# SCH_Power_board_2023-06-05.net
KiCad netlist of a schematic drawn in EasyEDA
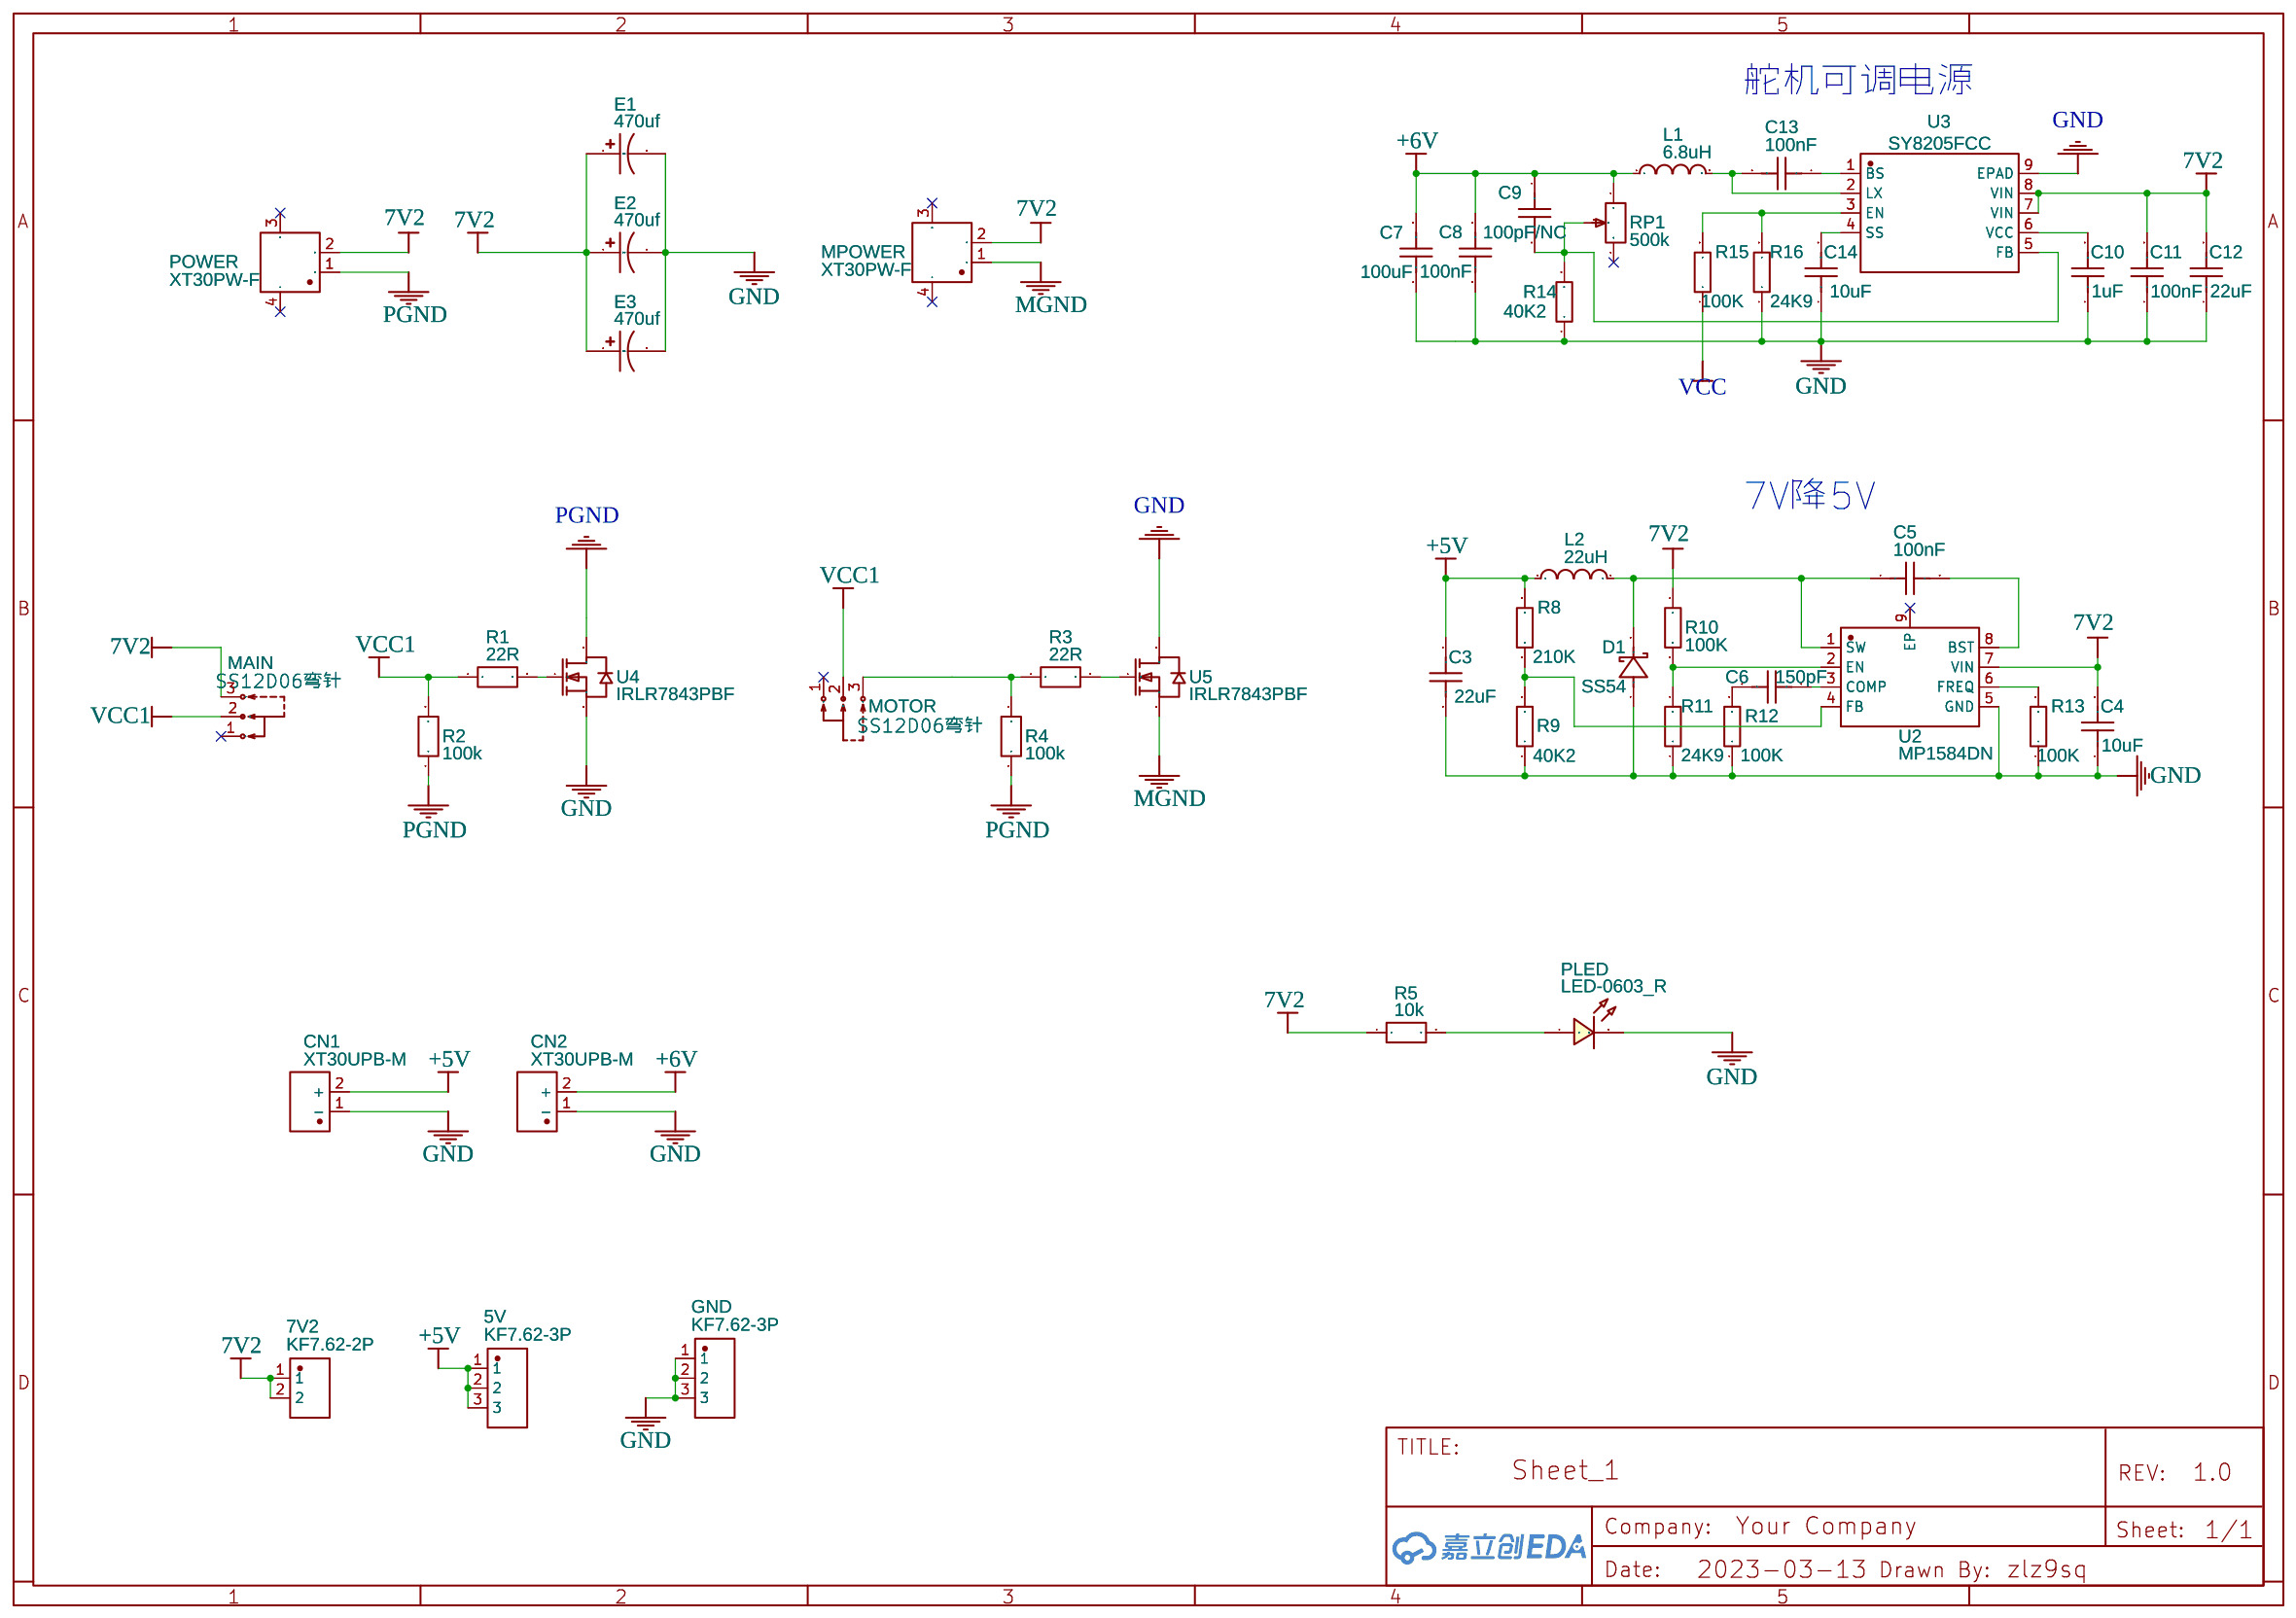
[diagram p0: schematic sheet]

(export (version "E")
  (design (tool "Eeschema 10.0.6"))
  (components
    (comp (ref "5V")
      (value "KF7.62-3P")
      (fields (field (name "BOM_Supplier Part") "C707825"))
      (libsource (lib "") (part "KF7.62-3P"))
    )
    (comp (ref "7V2")
      (value "KF7.62-2P")
      (fields (field (name "BOM_Supplier Part") "C707824"))
      (libsource (lib "") (part "KF7.62-2P"))
    )
    (comp (ref "C3") (value "22uF") (libsource (lib "") (part "C_0603_US_1")))
    (comp (ref "C4") (value "10uF") (libsource (lib "") (part "C_0603_US")))
    (comp (ref "C5") (value "100nF") (libsource (lib "") (part "C_0603_US_3")))
    (comp (ref "C6") (value "150pF") (libsource (lib "") (part "C_0603_US_2")))
    (comp (ref "C7")
      (value "100uF")
      (fields
        (field (name "BOM_Manufacturer Part") "C1210X7R475K630NT")
        (field (name "BOM_Supplier Part") "C2911397")
      )
      (libsource (lib "") (part "C1210X7R475K630NT"))
    )
    (comp (ref "C8") (value "100nF") (libsource (lib "") (part "C_0603_US_1")))
    (comp (ref "C9") (value "100pF/NC") (libsource (lib "") (part "C_0603_US_1")))
    (comp (ref "C10") (value "1uF") (libsource (lib "") (part "C_0603_US")))
    (comp (ref "C11") (value "100nF") (libsource (lib "") (part "C_0603_US")))
    (comp (ref "C12") (value "22uF") (libsource (lib "") (part "C_0603_US")))
    (comp (ref "C13") (value "100nF") (libsource (lib "") (part "C_0603_US_2")))
    (comp (ref "C14") (value "10uF") (libsource (lib "") (part "C_0603_US")))
    (comp (ref "CN1")
      (value "XT30UPB-M")
      (fields (field (name "BOM_Supplier Part") "C428721"))
      (libsource (lib "") (part "XT30UPB-M"))
    )
    (comp (ref "CN2")
      (value "XT30UPB-M")
      (fields (field (name "BOM_Supplier Part") "C428721"))
      (libsource (lib "") (part "XT30UPB-M"))
    )
    (comp (ref "D1")
      (value "SS54")
      (fields (field (name "BOM_Manufacturer Part") "SS54G") (field (name "BOM_Supplier Part") "C719150"))
      (libsource (lib "") (part "SS54G"))
    )
    (comp (ref "E1") (value "470uf") (libsource (lib "") (part "CE_TH_D5.0×F2.0_US")))
    (comp (ref "E2") (value "470uf") (libsource (lib "") (part "CE_TH_D5.0×F2.0_US")))
    (comp (ref "E3") (value "470uf") (libsource (lib "") (part "CE_TH_D5.0×F2.0_US")))
    (comp (ref "GND")
      (value "KF7.62-3P")
      (fields (field (name "BOM_Supplier Part") "C707825"))
      (libsource (lib "") (part "KF7.62-3P_1"))
    )
    (comp (ref "L1")
      (value "6.8uH")
      (fields
        (field (name "BOM_Manufacturer Part") "FXL0630-8R2-M")
        (field (name "BOM_Supplier Part") "C167222")
      )
      (libsource (lib "") (part "FXL0630-8R2-M"))
    )
    (comp (ref "L2")
      (value "22uH")
      (fields
        (field (name "BOM_Manufacturer Part") "FXL0630-8R2-M")
        (field (name "BOM_Supplier Part") "C167222")
      )
      (libsource (lib "") (part "FXL0630-8R2-M"))
    )
    (comp (ref "MAIN")
      (value "SS12D06弯针")
      (fields (field (name "BOM_Supplier Part") "C9900027365"))
      (libsource (lib "") (part "SS12D06弯针"))
    )
    (comp (ref "MOTOR")
      (value "SS12D06弯针")
      (fields (field (name "BOM_Supplier Part") "C9900027365"))
      (libsource (lib "") (part "SS12D06弯针_1"))
    )
    (comp (ref "MPOWER")
      (value "XT30PW-F")
      (fields (field (name "BOM_Supplier Part") "C2913282"))
      (libsource (lib "") (part "XT30PW-F_1"))
    )
    (comp (ref "PLED")
      (value "LED-0603_R")
      (fields
        (field (name "BOM_Manufacturer Part") "19-217/R6C-AL1M2VY/3T")
        (field (name "BOM_Supplier Part") "C72044")
      )
      (libsource (lib "") (part "LED-0603_R"))
    )
    (comp (ref "POWER")
      (value "XT30PW-F")
      (fields (field (name "BOM_Supplier Part") "C2913282"))
      (libsource (lib "") (part "XT30PW-F"))
    )
    (comp (ref "R1") (value "22R") (libsource (lib "") (part "R_0603_EU")))
    (comp (ref "R2") (value "100k") (libsource (lib "") (part "R_0603_EU_1")))
    (comp (ref "R3") (value "22R") (libsource (lib "") (part "R_0603_EU")))
    (comp (ref "R4") (value "100k") (libsource (lib "") (part "R_0603_EU_1")))
    (comp (ref "R5") (value "10k") (libsource (lib "") (part "R_0603_EU")))
    (comp (ref "R8")
      (value "210K")
      (fields
        (field (name "BOM_Manufacturer Part") "QR0603B47KP05")
        (field (name "BOM_Supplier Part") "C176123")
      )
      (libsource (lib "") (part "QR0603B47KP05"))
    )
    (comp (ref "R9")
      (value "40K2")
      (fields
        (field (name "BOM_Manufacturer Part") "QR0603B47KP05")
        (field (name "BOM_Supplier Part") "C176123")
      )
      (libsource (lib "") (part "QR0603B47KP05"))
    )
    (comp (ref "R10")
      (value "100K")
      (fields
        (field (name "BOM_Manufacturer Part") "QR0603B47KP05")
        (field (name "BOM_Supplier Part") "C176123")
      )
      (libsource (lib "") (part "QR0603B47KP05_1"))
    )
    (comp (ref "R11")
      (value "24K9")
      (fields
        (field (name "BOM_Manufacturer Part") "QR0603B47KP05")
        (field (name "BOM_Supplier Part") "C176123")
      )
      (libsource (lib "") (part "QR0603B47KP05"))
    )
    (comp (ref "R12")
      (value "100K")
      (fields
        (field (name "BOM_Manufacturer Part") "QR0603B47KP05")
        (field (name "BOM_Supplier Part") "C176123")
      )
      (libsource (lib "") (part "QR0603B47KP05"))
    )
    (comp (ref "R13")
      (value "100K")
      (fields
        (field (name "BOM_Manufacturer Part") "QR0603B47KP05")
        (field (name "BOM_Supplier Part") "C176123")
      )
      (libsource (lib "") (part "QR0603B47KP05"))
    )
    (comp (ref "R14")
      (value "40K2")
      (fields
        (field (name "BOM_Manufacturer Part") "QR0603B47KP05")
        (field (name "BOM_Supplier Part") "C176123")
      )
      (libsource (lib "") (part "QR0603B47KP05"))
    )
    (comp (ref "R15")
      (value "100K")
      (fields
        (field (name "BOM_Manufacturer Part") "QR0603B47KP05")
        (field (name "BOM_Supplier Part") "C176123")
      )
      (libsource (lib "") (part "QR0603B47KP05"))
    )
    (comp (ref "R16")
      (value "24K9")
      (fields
        (field (name "BOM_Manufacturer Part") "QR0603B47KP05")
        (field (name "BOM_Supplier Part") "C176123")
      )
      (libsource (lib "") (part "QR0603B47KP05"))
    )
    (comp (ref "RP1")
      (value "500k")
      (fields
        (field (name "BOM_Manufacturer Part") "多圈电位器3296W顶调20K")
        (field (name "BOM_Supplier Part") "C9900006166")
      )
      (libsource (lib "") (part "多圈电位器3296W顶调20K"))
    )
    (comp (ref "U2")
      (value "MP1584DN")
      (fields (field (name "BOM_Supplier Part") "C9900012540"))
      (libsource (lib "") (part "MP1584DN"))
    )
    (comp (ref "U3")
      (value "SY8205FCC")
      (fields (field (name "BOM_Supplier Part") "C111875"))
      (libsource (lib "") (part "SY8205FCC"))
    )
    (comp (ref "U4")
      (value "IRLR7843PBF")
      (fields (field (name "BOM_Supplier Part") "C3294487"))
      (libsource (lib "") (part "IRLR7843PBF"))
    )
    (comp (ref "U5")
      (value "IRLR7843PBF")
      (fields (field (name "BOM_Supplier Part") "C3294487"))
      (libsource (lib "") (part "IRLR7843PBF"))
    )
  )
  (nets
    (net (code "1") (name "+5V") (class "Default")
      (node (ref "5V") (pin "1") (pinfunction "1_1") (pintype "unspecified"))
      (node (ref "5V") (pin "2") (pinfunction "2_2") (pintype "unspecified"))
      (node (ref "5V") (pin "3") (pinfunction "3_3") (pintype "unspecified"))
      (node (ref "C3") (pin "1") (pinfunction "1_1") (pintype "unspecified"))
      (node (ref "CN1") (pin "2") (pinfunction "+_2") (pintype "unspecified"))
      (node (ref "L2") (pin "1") (pinfunction "1_1") (pintype "unspecified"))
      (node (ref "R8") (pin "2") (pinfunction "2_2") (pintype "unspecified"))
    )
    (net (code "2") (name "+6V") (class "Default")
      (node (ref "C7") (pin "2") (pinfunction "2_2") (pintype "unspecified"))
      (node (ref "C8") (pin "1") (pinfunction "1_1") (pintype "unspecified"))
      (node (ref "C9") (pin "1") (pinfunction "1_1") (pintype "unspecified"))
      (node (ref "CN2") (pin "2") (pinfunction "+_2") (pintype "unspecified"))
      (node (ref "L1") (pin "1") (pinfunction "1_1") (pintype "unspecified"))
      (node (ref "RP1") (pin "1") (pinfunction "1_1") (pintype "input"))
    )
    (net (code "3") (name "7V2") (class "Default")
      (node (ref "7V2") (pin "1") (pinfunction "1_1") (pintype "unspecified"))
      (node (ref "7V2") (pin "2") (pinfunction "2_2") (pintype "unspecified"))
      (node (ref "C11") (pin "2") (pinfunction "2_2") (pintype "unspecified"))
      (node (ref "C12") (pin "2") (pinfunction "2_2") (pintype "unspecified"))
      (node (ref "C4") (pin "2") (pinfunction "2_2") (pintype "unspecified"))
      (node (ref "E1") (pin "1") (pinfunction "1_1") (pintype "unspecified"))
      (node (ref "E2") (pin "1") (pinfunction "1_1") (pintype "unspecified"))
      (node (ref "E3") (pin "1") (pinfunction "1_1") (pintype "unspecified"))
      (node (ref "MAIN") (pin "3") (pinfunction "3_3") (pintype "unspecified"))
      (node (ref "MPOWER") (pin "2") (pinfunction "2_2") (pintype "unspecified"))
      (node (ref "POWER") (pin "2") (pinfunction "2_2") (pintype "unspecified"))
      (node (ref "R10") (pin "1") (pinfunction "1_1") (pintype "unspecified"))
      (node (ref "R5") (pin "1") (pinfunction "1_1") (pintype "unspecified"))
      (node (ref "U2") (pin "7") (pinfunction "VIN_7") (pintype "unspecified"))
      (node (ref "U3") (pin "7") (pinfunction "VIN_7") (pintype "unspecified"))
      (node (ref "U3") (pin "8") (pinfunction "VIN_8") (pintype "unspecified"))
    )
    (net (code "4") (name "GND") (class "Default")
      (node (ref "C10") (pin "1") (pinfunction "1_1") (pintype "unspecified"))
      (node (ref "C11") (pin "1") (pinfunction "1_1") (pintype "unspecified"))
      (node (ref "C12") (pin "1") (pinfunction "1_1") (pintype "unspecified"))
      (node (ref "C14") (pin "1") (pinfunction "1_1") (pintype "unspecified"))
      (node (ref "C3") (pin "2") (pinfunction "2_2") (pintype "unspecified"))
      (node (ref "C4") (pin "1") (pinfunction "1_1") (pintype "unspecified"))
      (node (ref "C7") (pin "1") (pinfunction "1_1") (pintype "unspecified"))
      (node (ref "C8") (pin "2") (pinfunction "2_2") (pintype "unspecified"))
      (node (ref "CN1") (pin "1") (pinfunction "-_1") (pintype "unspecified"))
      (node (ref "CN2") (pin "1") (pinfunction "-_1") (pintype "unspecified"))
      (node (ref "D1") (pin "1") (pinfunction "A_1") (pintype "unspecified"))
      (node (ref "E1") (pin "2") (pinfunction "2_2") (pintype "unspecified"))
      (node (ref "E2") (pin "2") (pinfunction "2_2") (pintype "unspecified"))
      (node (ref "E3") (pin "2") (pinfunction "2_2") (pintype "unspecified"))
      (node (ref "GND") (pin "1") (pinfunction "1_1") (pintype "unspecified"))
      (node (ref "GND") (pin "2") (pinfunction "2_2") (pintype "unspecified"))
      (node (ref "GND") (pin "3") (pinfunction "3_3") (pintype "unspecified"))
      (node (ref "PLED") (pin "2") (pinfunction "2_2") (pintype "unspecified"))
      (node (ref "R11") (pin "1") (pinfunction "1_1") (pintype "unspecified"))
      (node (ref "R12") (pin "1") (pinfunction "1_1") (pintype "unspecified"))
      (node (ref "R13") (pin "1") (pinfunction "1_1") (pintype "unspecified"))
      (node (ref "R14") (pin "1") (pinfunction "1_1") (pintype "unspecified"))
      (node (ref "R16") (pin "1") (pinfunction "1_1") (pintype "unspecified"))
      (node (ref "R9") (pin "1") (pinfunction "1_1") (pintype "unspecified"))
      (node (ref "U2") (pin "5") (pinfunction "GND_5") (pintype "unspecified"))
      (node (ref "U3") (pin "9") (pinfunction "EPAD_9") (pintype "unspecified"))
      (node (ref "U4") (pin "3") (pinfunction "S_3") (pintype "unspecified"))
      (node (ref "U5") (pin "2") (pinfunction "D_2") (pintype "unspecified"))
    )
    (net (code "5") (name "MGND") (class "Default")
      (node (ref "MPOWER") (pin "1") (pinfunction "1_1") (pintype "unspecified"))
      (node (ref "U5") (pin "3") (pinfunction "S_3") (pintype "unspecified"))
    )
    (net (code "6") (name "Net-(C6-Pad2)") (class "Default")
      (node (ref "C6") (pin "2") (pinfunction "2_2") (pintype "unspecified"))
      (node (ref "R12") (pin "2") (pinfunction "2_2") (pintype "unspecified"))
    )
    (net (code "7") (name "Net-(D1-K)") (class "Default")
      (node (ref "C5") (pin "1") (pinfunction "1_1") (pintype "unspecified"))
      (node (ref "D1") (pin "2") (pinfunction "K_2") (pintype "unspecified"))
      (node (ref "L2") (pin "2") (pinfunction "2_2") (pintype "unspecified"))
      (node (ref "U2") (pin "1") (pinfunction "SW_1") (pintype "unspecified"))
    )
    (net (code "8") (name "Net-(MOTOR-Pad3)") (class "Default")
      (node (ref "MOTOR") (pin "3") (pinfunction "3_3") (pintype "unspecified"))
      (node (ref "R3") (pin "1") (pinfunction "1_1") (pintype "unspecified"))
      (node (ref "R4") (pin "2") (pinfunction "2_2") (pintype "unspecified"))
    )
    (net (code "9") (name "Net-(PLED-Pad1)") (class "Default")
      (node (ref "PLED") (pin "1") (pinfunction "1_1") (pintype "unspecified"))
      (node (ref "R5") (pin "2") (pinfunction "2_2") (pintype "unspecified"))
    )
    (net (code "10") (name "Net-(U2-BST)") (class "Default")
      (node (ref "C5") (pin "2") (pinfunction "2_2") (pintype "unspecified"))
      (node (ref "U2") (pin "8") (pinfunction "BST_8") (pintype "unspecified"))
    )
    (net (code "11") (name "Net-(U2-COMP)") (class "Default")
      (node (ref "C6") (pin "1") (pinfunction "1_1") (pintype "unspecified"))
      (node (ref "U2") (pin "3") (pinfunction "COMP_3") (pintype "unspecified"))
    )
    (net (code "12") (name "Net-(U2-EN)") (class "Default")
      (node (ref "R10") (pin "2") (pinfunction "2_2") (pintype "unspecified"))
      (node (ref "R11") (pin "2") (pinfunction "2_2") (pintype "unspecified"))
      (node (ref "U2") (pin "2") (pinfunction "EN_2") (pintype "unspecified"))
    )
    (net (code "13") (name "Net-(U2-FB)") (class "Default")
      (node (ref "R8") (pin "1") (pinfunction "1_1") (pintype "unspecified"))
      (node (ref "R9") (pin "2") (pinfunction "2_2") (pintype "unspecified"))
      (node (ref "U2") (pin "4") (pinfunction "FB_4") (pintype "unspecified"))
    )
    (net (code "14") (name "Net-(U2-FREQ)") (class "Default")
      (node (ref "R13") (pin "2") (pinfunction "2_2") (pintype "unspecified"))
      (node (ref "U2") (pin "6") (pinfunction "FREQ_6") (pintype "unspecified"))
    )
    (net (code "15") (name "Net-(U3-BS)") (class "Default")
      (node (ref "C13") (pin "1") (pinfunction "1_1") (pintype "unspecified"))
      (node (ref "U3") (pin "1") (pinfunction "BS_1") (pintype "unspecified"))
    )
    (net (code "16") (name "Net-(U3-EN)") (class "Default")
      (node (ref "R15") (pin "2") (pinfunction "2_2") (pintype "unspecified"))
      (node (ref "R16") (pin "2") (pinfunction "2_2") (pintype "unspecified"))
      (node (ref "U3") (pin "3") (pinfunction "EN_3") (pintype "unspecified"))
    )
    (net (code "17") (name "Net-(U3-FB)") (class "Default")
      (node (ref "C9") (pin "2") (pinfunction "2_2") (pintype "unspecified"))
      (node (ref "R14") (pin "2") (pinfunction "2_2") (pintype "unspecified"))
      (node (ref "RP1") (pin "2") (pinfunction "2_2") (pintype "input"))
      (node (ref "U3") (pin "5") (pinfunction "FB_5") (pintype "unspecified"))
    )
    (net (code "18") (name "Net-(U3-LX)") (class "Default")
      (node (ref "C13") (pin "2") (pinfunction "2_2") (pintype "unspecified"))
      (node (ref "L1") (pin "2") (pinfunction "2_2") (pintype "unspecified"))
      (node (ref "U3") (pin "2") (pinfunction "LX_2") (pintype "unspecified"))
    )
    (net (code "19") (name "Net-(U3-SS)") (class "Default")
      (node (ref "C14") (pin "2") (pinfunction "2_2") (pintype "unspecified"))
      (node (ref "U3") (pin "4") (pinfunction "SS_4") (pintype "unspecified"))
    )
    (net (code "20") (name "Net-(U3-VCC)") (class "Default")
      (node (ref "C10") (pin "2") (pinfunction "2_2") (pintype "unspecified"))
      (node (ref "U3") (pin "6") (pinfunction "VCC_6") (pintype "unspecified"))
    )
    (net (code "21") (name "Net-(U4-G)") (class "Default")
      (node (ref "R1") (pin "2") (pinfunction "2_2") (pintype "unspecified"))
      (node (ref "U4") (pin "1") (pinfunction "G_1") (pintype "unspecified"))
    )
    (net (code "22") (name "Net-(U5-G)") (class "Default")
      (node (ref "R3") (pin "2") (pinfunction "2_2") (pintype "unspecified"))
      (node (ref "U5") (pin "1") (pinfunction "G_1") (pintype "unspecified"))
    )
    (net (code "23") (name "PGND") (class "Default")
      (node (ref "POWER") (pin "1") (pinfunction "1_1") (pintype "unspecified"))
      (node (ref "R2") (pin "1") (pinfunction "1_1") (pintype "unspecified"))
      (node (ref "R4") (pin "1") (pinfunction "1_1") (pintype "unspecified"))
      (node (ref "U4") (pin "2") (pinfunction "D_2") (pintype "unspecified"))
    )
    (net (code "24") (name "VCC") (class "Default")
      (node (ref "R15") (pin "1") (pinfunction "1_1") (pintype "unspecified"))
    )
    (net (code "25") (name "VCC1") (class "Default")
      (node (ref "MAIN") (pin "2") (pinfunction "2_2") (pintype "unspecified"))
      (node (ref "MOTOR") (pin "2") (pinfunction "2_2") (pintype "unspecified"))
      (node (ref "R1") (pin "1") (pinfunction "1_1") (pintype "unspecified"))
      (node (ref "R2") (pin "2") (pinfunction "2_2") (pintype "unspecified"))
    )
    (net (code "26") (name "unconnected-(MAIN-Pad1)") (class "Default")
      (node (ref "MAIN") (pin "1") (pinfunction "1_1") (pintype "unspecified+no_connect"))
    )
    (net (code "27") (name "unconnected-(MOTOR-Pad1)") (class "Default")
      (node (ref "MOTOR") (pin "1") (pinfunction "1_1") (pintype "unspecified+no_connect"))
    )
    (net (code "28") (name "unconnected-(MPOWER-Pad3)") (class "Default")
      (node (ref "MPOWER") (pin "3") (pinfunction "3_3") (pintype "unspecified+no_connect"))
    )
    (net (code "29") (name "unconnected-(MPOWER-Pad4)") (class "Default")
      (node (ref "MPOWER") (pin "4") (pinfunction "4_4") (pintype "unspecified+no_connect"))
    )
    (net (code "30") (name "unconnected-(POWER-Pad3)") (class "Default")
      (node (ref "POWER") (pin "3") (pinfunction "3_3") (pintype "unspecified+no_connect"))
    )
    (net (code "31") (name "unconnected-(POWER-Pad4)") (class "Default")
      (node (ref "POWER") (pin "4") (pinfunction "4_4") (pintype "unspecified+no_connect"))
    )
    (net (code "32") (name "unconnected-(RP1-Pad3)") (class "Default")
      (node (ref "RP1") (pin "3") (pinfunction "3_3") (pintype "input+no_connect"))
    )
    (net (code "33") (name "unconnected-(U2-EP-Pad9)") (class "Default")
      (node (ref "U2") (pin "9") (pinfunction "EP_9") (pintype "unspecified+no_connect"))
    )
  )
)
